# MicroController_Main.net
KiCad netlist of a schematic drawn in Altium Designer
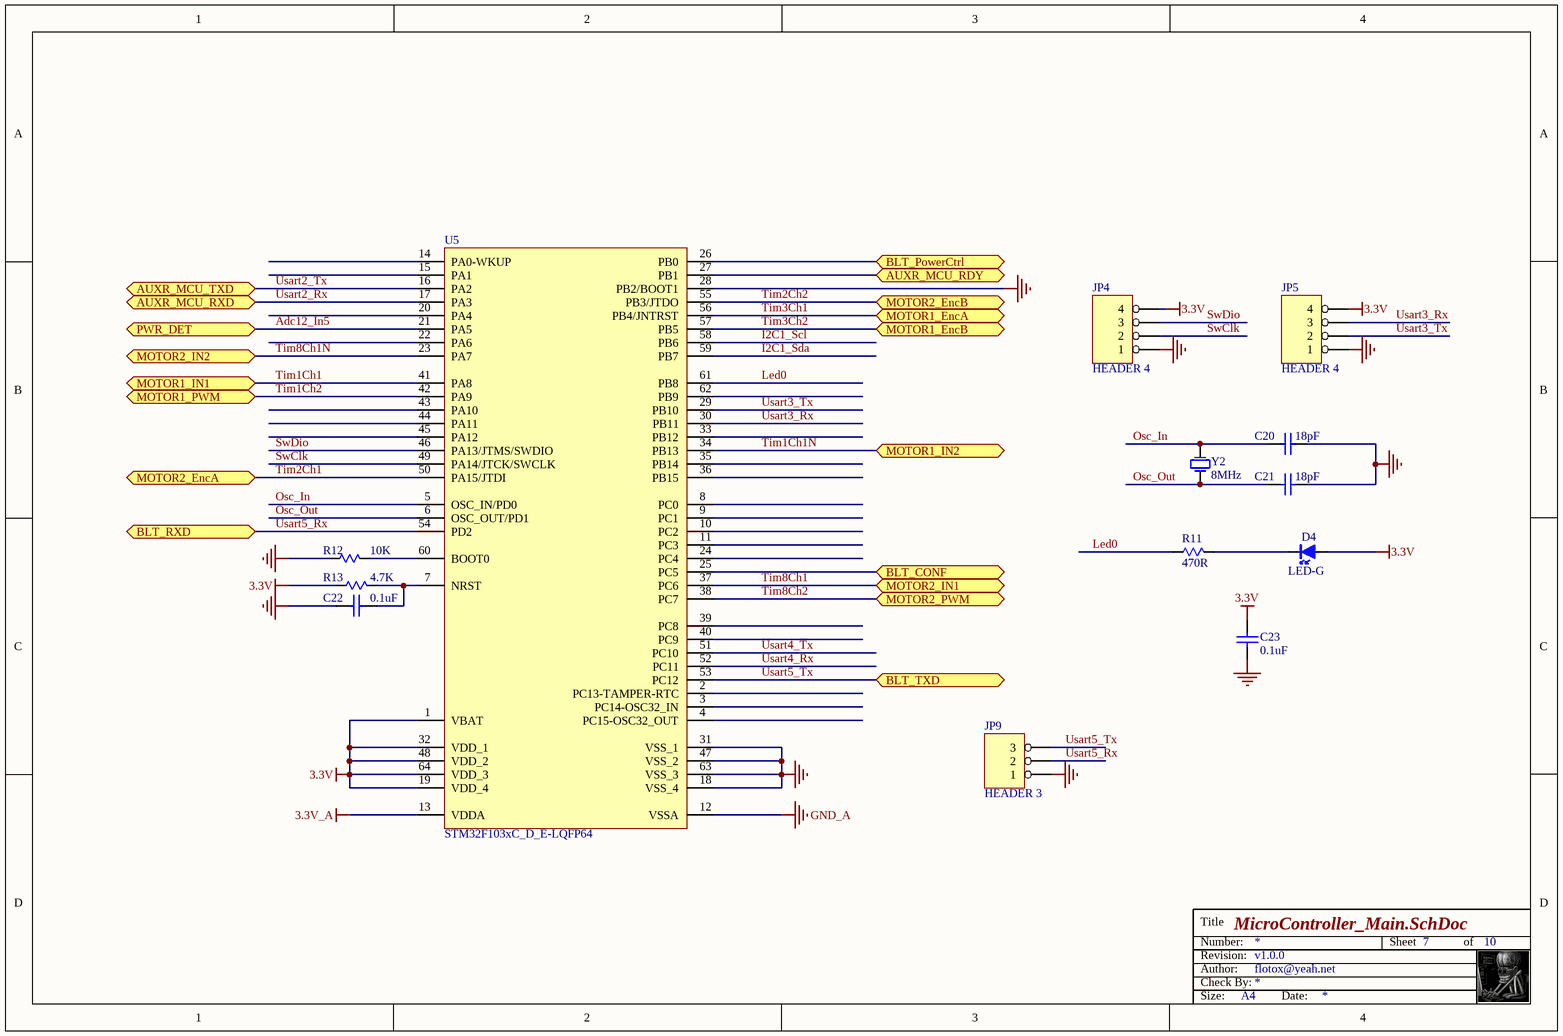
[diagram p0: MicroController_Main.SchDoc]

(export (version "E")
  (design (tool "Eeschema 10.0.6"))
  (components
    (comp (ref "C20")
      (value "18pF")
      (footprint "C0603-S")
      (description "Capacitor")
      (libsource (lib "Passive Components Class") (part "CAP"))
    )
    (comp (ref "C21")
      (value "18pF")
      (footprint "C0603-S")
      (description "Capacitor")
      (libsource (lib "Passive Components Class") (part "CAP"))
    )
    (comp (ref "C22")
      (value "0.1uF")
      (footprint "C0603-S")
      (description "Capacitor")
      (libsource (lib "Passive Components Class") (part "CAP"))
    )
    (comp (ref "C23")
      (value "0.1uF")
      (footprint "C0603-S")
      (description "Capacitor")
      (libsource (lib "Passive Components Class") (part "CAP"))
    )
    (comp (ref "D4")
      (value "LED-G")
      (footprint "LED0603")
      (description "Light Emitting Diode")
      (libsource (lib "Passive Components Class") (part "LED"))
    )
    (comp (ref "JP4")
      (value "HEADER 4")
      (footprint "HDR1X4")
      (libsource (lib "Connector Class") (part "HEADER 4"))
    )
    (comp (ref "JP5")
      (value "HEADER 4")
      (footprint "SPOX-4P")
      (libsource (lib "Connector Class") (part "HEADER 4"))
    )
    (comp (ref "JP9")
      (value "HEADER 3")
      (footprint "HDR1X3")
      (libsource (lib "Connector Class") (part "HEADER 3"))
    )
    (comp (ref "R11")
      (value "470R")
      (footprint "R0603-S")
      (description "Resistor")
      (libsource (lib "Passive Components Class") (part "RES"))
    )
    (comp (ref "R12")
      (value "10K")
      (footprint "R0603-S")
      (description "Resistor")
      (libsource (lib "Passive Components Class") (part "RES"))
    )
    (comp (ref "R13")
      (value "4.7K")
      (footprint "R0603-S")
      (description "Resistor")
      (libsource (lib "Passive Components Class") (part "RES"))
    )
    (comp (ref "U5")
      (value "STM32F103xC_D_E-LQFP64")
      (footprint "LQFP10X10-64")
      (libsource (lib "Microcontrollers Class") (part "STM32F103xC_D_E-LQFP64"))
    )
    (comp (ref "Y2")
      (value "8MHz")
      (footprint "XTAL-49SMD")
      (description "Crystals")
      (libsource (lib "Passive Components Class") (part "XTAL-CRYSTALS"))
    )
  )
  (nets
    (net (code "1") (name "/AUXR_MCU_RDY") (class "Default")
      (node (ref "U5") (pin "27") (pinfunction "PB1_27") (pintype "passive"))
    )
    (net (code "2") (name "/Adc12_In5") (class "Default")
      (node (ref "U5") (pin "21") (pinfunction "PA5_21") (pintype "passive"))
    )
    (net (code "3") (name "/BLT_CONF") (class "Default")
      (node (ref "U5") (pin "25") (pinfunction "PC5_25") (pintype "passive"))
    )
    (net (code "4") (name "/BLT_PowerCtrl") (class "Default")
      (node (ref "U5") (pin "26") (pinfunction "PB0_26") (pintype "passive"))
    )
    (net (code "5") (name "/I2C1_Scl") (class "Default")
      (node (ref "U5") (pin "58") (pinfunction "PB6_58") (pintype "passive"))
    )
    (net (code "6") (name "/I2C1_Sda") (class "Default")
      (node (ref "U5") (pin "59") (pinfunction "PB7_59") (pintype "passive"))
    )
    (net (code "7") (name "/Led0") (class "Default")
      (node (ref "R11") (pin "2") (pinfunction "2_2") (pintype "passive"))
      (node (ref "U5") (pin "61") (pinfunction "PB8_61") (pintype "passive"))
    )
    (net (code "8") (name "/Osc_In") (class "Default")
      (node (ref "C20") (pin "2") (pinfunction "2_2") (pintype "passive"))
      (node (ref "U5") (pin "5") (pinfunction "OSC_IN/PD0_5") (pintype "passive"))
      (node (ref "Y2") (pin "1") (pinfunction "OSC1_1") (pintype "passive"))
    )
    (net (code "9") (name "/Osc_Out") (class "Default")
      (node (ref "C21") (pin "2") (pinfunction "2_2") (pintype "passive"))
      (node (ref "U5") (pin "6") (pinfunction "OSC_OUT/PD1_6") (pintype "passive"))
      (node (ref "Y2") (pin "2") (pinfunction "OSC2_2") (pintype "passive"))
    )
    (net (code "10") (name "/SwClk") (class "Default")
      (node (ref "JP4") (pin "2") (pinfunction "2_2") (pintype "passive"))
      (node (ref "U5") (pin "49") (pinfunction "PA14/JTCK/SWCLK_49") (pintype "passive"))
    )
    (net (code "11") (name "/SwDio") (class "Default")
      (node (ref "JP4") (pin "3") (pinfunction "3_3") (pintype "passive"))
      (node (ref "U5") (pin "46") (pinfunction "PA13/JTMS/SWDIO_46") (pintype "passive"))
    )
    (net (code "12") (name "/Tim1Ch1") (class "Default")
      (node (ref "U5") (pin "41") (pinfunction "PA8_41") (pintype "passive"))
    )
    (net (code "13") (name "/Tim1Ch1N") (class "Default")
      (node (ref "U5") (pin "34") (pinfunction "PB13_34") (pintype "passive"))
    )
    (net (code "14") (name "/Tim1Ch2") (class "Default")
      (node (ref "U5") (pin "42") (pinfunction "PA9_42") (pintype "passive"))
    )
    (net (code "15") (name "/Tim2Ch1") (class "Default")
      (node (ref "U5") (pin "50") (pinfunction "PA15/JTDI_50") (pintype "passive"))
    )
    (net (code "16") (name "/Tim2Ch2") (class "Default")
      (node (ref "U5") (pin "55") (pinfunction "PB3/JTDO_55") (pintype "passive"))
    )
    (net (code "17") (name "/Tim3Ch1") (class "Default")
      (node (ref "U5") (pin "56") (pinfunction "PB4/JNTRST_56") (pintype "passive"))
    )
    (net (code "18") (name "/Tim3Ch2") (class "Default")
      (node (ref "U5") (pin "57") (pinfunction "PB5_57") (pintype "passive"))
    )
    (net (code "19") (name "/Tim8Ch1") (class "Default")
      (node (ref "U5") (pin "37") (pinfunction "PC6_37") (pintype "passive"))
    )
    (net (code "20") (name "/Tim8Ch1N") (class "Default")
      (node (ref "U5") (pin "23") (pinfunction "PA7_23") (pintype "passive"))
    )
    (net (code "21") (name "/Tim8Ch2") (class "Default")
      (node (ref "U5") (pin "38") (pinfunction "PC7_38") (pintype "passive"))
    )
    (net (code "22") (name "/Usart2_Rx") (class "Default")
      (node (ref "U5") (pin "17") (pinfunction "PA3_17") (pintype "passive"))
    )
    (net (code "23") (name "/Usart2_Tx") (class "Default")
      (node (ref "U5") (pin "16") (pinfunction "PA2_16") (pintype "passive"))
    )
    (net (code "24") (name "/Usart3_Rx") (class "Default")
      (node (ref "JP5") (pin "3") (pinfunction "3_3") (pintype "passive"))
      (node (ref "U5") (pin "30") (pinfunction "PB11_30") (pintype "passive"))
    )
    (net (code "25") (name "/Usart3_Tx") (class "Default")
      (node (ref "JP5") (pin "2") (pinfunction "2_2") (pintype "passive"))
      (node (ref "U5") (pin "29") (pinfunction "PB10_29") (pintype "passive"))
    )
    (net (code "26") (name "/Usart4_Rx") (class "Default")
      (node (ref "U5") (pin "52") (pinfunction "PC11_52") (pintype "passive"))
    )
    (net (code "27") (name "/Usart4_Tx") (class "Default")
      (node (ref "U5") (pin "51") (pinfunction "PC10_51") (pintype "passive"))
    )
    (net (code "28") (name "/Usart5_Rx") (class "Default")
      (node (ref "JP9") (pin "2") (pinfunction "2_2") (pintype "passive"))
      (node (ref "U5") (pin "54") (pinfunction "PD2_54") (pintype "passive"))
    )
    (net (code "29") (name "/Usart5_Tx") (class "Default")
      (node (ref "JP9") (pin "3") (pinfunction "3_3") (pintype "passive"))
      (node (ref "U5") (pin "53") (pinfunction "PC12_53") (pintype "passive"))
    )
    (net (code "30") (name "3.3V") (class "Default")
      (node (ref "C23") (pin "2") (pinfunction "2_2") (pintype "passive"))
      (node (ref "D4") (pin "1") (pinfunction "A_1") (pintype "passive"))
      (node (ref "JP4") (pin "4") (pinfunction "4_4") (pintype "passive"))
      (node (ref "JP5") (pin "4") (pinfunction "4_4") (pintype "passive"))
      (node (ref "R13") (pin "2") (pinfunction "2_2") (pintype "passive"))
      (node (ref "U5") (pin "1") (pinfunction "VBAT_1") (pintype "passive"))
      (node (ref "U5") (pin "19") (pinfunction "VDD_4_19") (pintype "passive"))
      (node (ref "U5") (pin "32") (pinfunction "VDD_1_32") (pintype "passive"))
      (node (ref "U5") (pin "48") (pinfunction "VDD_2_48") (pintype "passive"))
      (node (ref "U5") (pin "64") (pinfunction "VDD_3_64") (pintype "passive"))
    )
    (net (code "31") (name "3.3V_A") (class "Default")
      (node (ref "U5") (pin "13") (pinfunction "VDDA_13") (pintype "passive"))
    )
    (net (code "32") (name "GND") (class "Default")
      (node (ref "C20") (pin "1") (pinfunction "1_1") (pintype "passive"))
      (node (ref "C21") (pin "1") (pinfunction "1_1") (pintype "passive"))
      (node (ref "C22") (pin "2") (pinfunction "2_2") (pintype "passive"))
      (node (ref "C23") (pin "1") (pinfunction "1_1") (pintype "passive"))
      (node (ref "JP4") (pin "1") (pinfunction "1_1") (pintype "passive"))
      (node (ref "JP5") (pin "1") (pinfunction "1_1") (pintype "passive"))
      (node (ref "JP9") (pin "1") (pinfunction "1_1") (pintype "passive"))
      (node (ref "R12") (pin "2") (pinfunction "2_2") (pintype "passive"))
      (node (ref "U5") (pin "18") (pinfunction "VSS_4_18") (pintype "passive"))
      (node (ref "U5") (pin "28") (pinfunction "PB2/BOOT1_28") (pintype "passive"))
      (node (ref "U5") (pin "31") (pinfunction "VSS_1_31") (pintype "passive"))
      (node (ref "U5") (pin "47") (pinfunction "VSS_2_47") (pintype "passive"))
      (node (ref "U5") (pin "63") (pinfunction "VSS_3_63") (pintype "passive"))
    )
    (net (code "33") (name "GND_A") (class "Default")
      (node (ref "U5") (pin "12") (pinfunction "VSSA_12") (pintype "passive"))
    )
    (net (code "34") (name "Net-(D4-K)") (class "Default")
      (node (ref "D4") (pin "2") (pinfunction "K_2") (pintype "passive"))
      (node (ref "R11") (pin "1") (pinfunction "1_1") (pintype "passive"))
    )
    (net (code "35") (name "Net-(U5-BOOT0)") (class "Default")
      (node (ref "R12") (pin "1") (pinfunction "1_1") (pintype "passive"))
      (node (ref "U5") (pin "60") (pinfunction "BOOT0_60") (pintype "passive"))
    )
    (net (code "36") (name "Net-(U5-NRST)") (class "Default")
      (node (ref "C22") (pin "1") (pinfunction "1_1") (pintype "passive"))
      (node (ref "R13") (pin "1") (pinfunction "1_1") (pintype "passive"))
      (node (ref "U5") (pin "7") (pinfunction "NRST_7") (pintype "passive"))
    )
    (net (code "37") (name "unconnected-(U5-PA0-WKUP-Pad14)") (class "Default")
      (node (ref "U5") (pin "14") (pinfunction "PA0-WKUP_14") (pintype "passive"))
    )
    (net (code "38") (name "unconnected-(U5-PA1-Pad15)") (class "Default")
      (node (ref "U5") (pin "15") (pinfunction "PA1_15") (pintype "passive"))
    )
    (net (code "39") (name "unconnected-(U5-PA4-Pad20)") (class "Default")
      (node (ref "U5") (pin "20") (pinfunction "PA4_20") (pintype "passive"))
    )
    (net (code "40") (name "unconnected-(U5-PA6-Pad22)") (class "Default")
      (node (ref "U5") (pin "22") (pinfunction "PA6_22") (pintype "passive"))
    )
    (net (code "41") (name "unconnected-(U5-PA10-Pad43)") (class "Default")
      (node (ref "U5") (pin "43") (pinfunction "PA10_43") (pintype "passive"))
    )
    (net (code "42") (name "unconnected-(U5-PA11-Pad44)") (class "Default")
      (node (ref "U5") (pin "44") (pinfunction "PA11_44") (pintype "passive"))
    )
    (net (code "43") (name "unconnected-(U5-PA12-Pad45)") (class "Default")
      (node (ref "U5") (pin "45") (pinfunction "PA12_45") (pintype "passive"))
    )
    (net (code "44") (name "unconnected-(U5-PB9-Pad62)") (class "Default")
      (node (ref "U5") (pin "62") (pinfunction "PB9_62") (pintype "passive"))
    )
    (net (code "45") (name "unconnected-(U5-PB12-Pad33)") (class "Default")
      (node (ref "U5") (pin "33") (pinfunction "PB12_33") (pintype "passive"))
    )
    (net (code "46") (name "unconnected-(U5-PB14-Pad35)") (class "Default")
      (node (ref "U5") (pin "35") (pinfunction "PB14_35") (pintype "passive"))
    )
    (net (code "47") (name "unconnected-(U5-PB15-Pad36)") (class "Default")
      (node (ref "U5") (pin "36") (pinfunction "PB15_36") (pintype "passive"))
    )
    (net (code "48") (name "unconnected-(U5-PC0-Pad8)") (class "Default")
      (node (ref "U5") (pin "8") (pinfunction "PC0_8") (pintype "passive"))
    )
    (net (code "49") (name "unconnected-(U5-PC1-Pad9)") (class "Default")
      (node (ref "U5") (pin "9") (pinfunction "PC1_9") (pintype "passive"))
    )
    (net (code "50") (name "unconnected-(U5-PC2-Pad10)") (class "Default")
      (node (ref "U5") (pin "10") (pinfunction "PC2_10") (pintype "passive"))
    )
    (net (code "51") (name "unconnected-(U5-PC3-Pad11)") (class "Default")
      (node (ref "U5") (pin "11") (pinfunction "PC3_11") (pintype "passive"))
    )
    (net (code "52") (name "unconnected-(U5-PC4-Pad24)") (class "Default")
      (node (ref "U5") (pin "24") (pinfunction "PC4_24") (pintype "passive"))
    )
    (net (code "53") (name "unconnected-(U5-PC8-Pad39)") (class "Default")
      (node (ref "U5") (pin "39") (pinfunction "PC8_39") (pintype "passive"))
    )
    (net (code "54") (name "unconnected-(U5-PC9-Pad40)") (class "Default")
      (node (ref "U5") (pin "40") (pinfunction "PC9_40") (pintype "passive"))
    )
    (net (code "55") (name "unconnected-(U5-PC13-TAMPER-RTC-Pad2)") (class "Default")
      (node (ref "U5") (pin "2") (pinfunction "PC13-TAMPER-RTC_2") (pintype "passive"))
    )
    (net (code "56") (name "unconnected-(U5-PC14-OSC32_IN-Pad3)") (class "Default")
      (node (ref "U5") (pin "3") (pinfunction "PC14-OSC32_IN_3") (pintype "passive"))
    )
    (net (code "57") (name "unconnected-(U5-PC15-OSC32_OUT-Pad4)") (class "Default")
      (node (ref "U5") (pin "4") (pinfunction "PC15-OSC32_OUT_4") (pintype "passive"))
    )
  )
)
